# FPGA_RGMII_Misc.net
KiCad netlist of a schematic drawn in Altium Designer
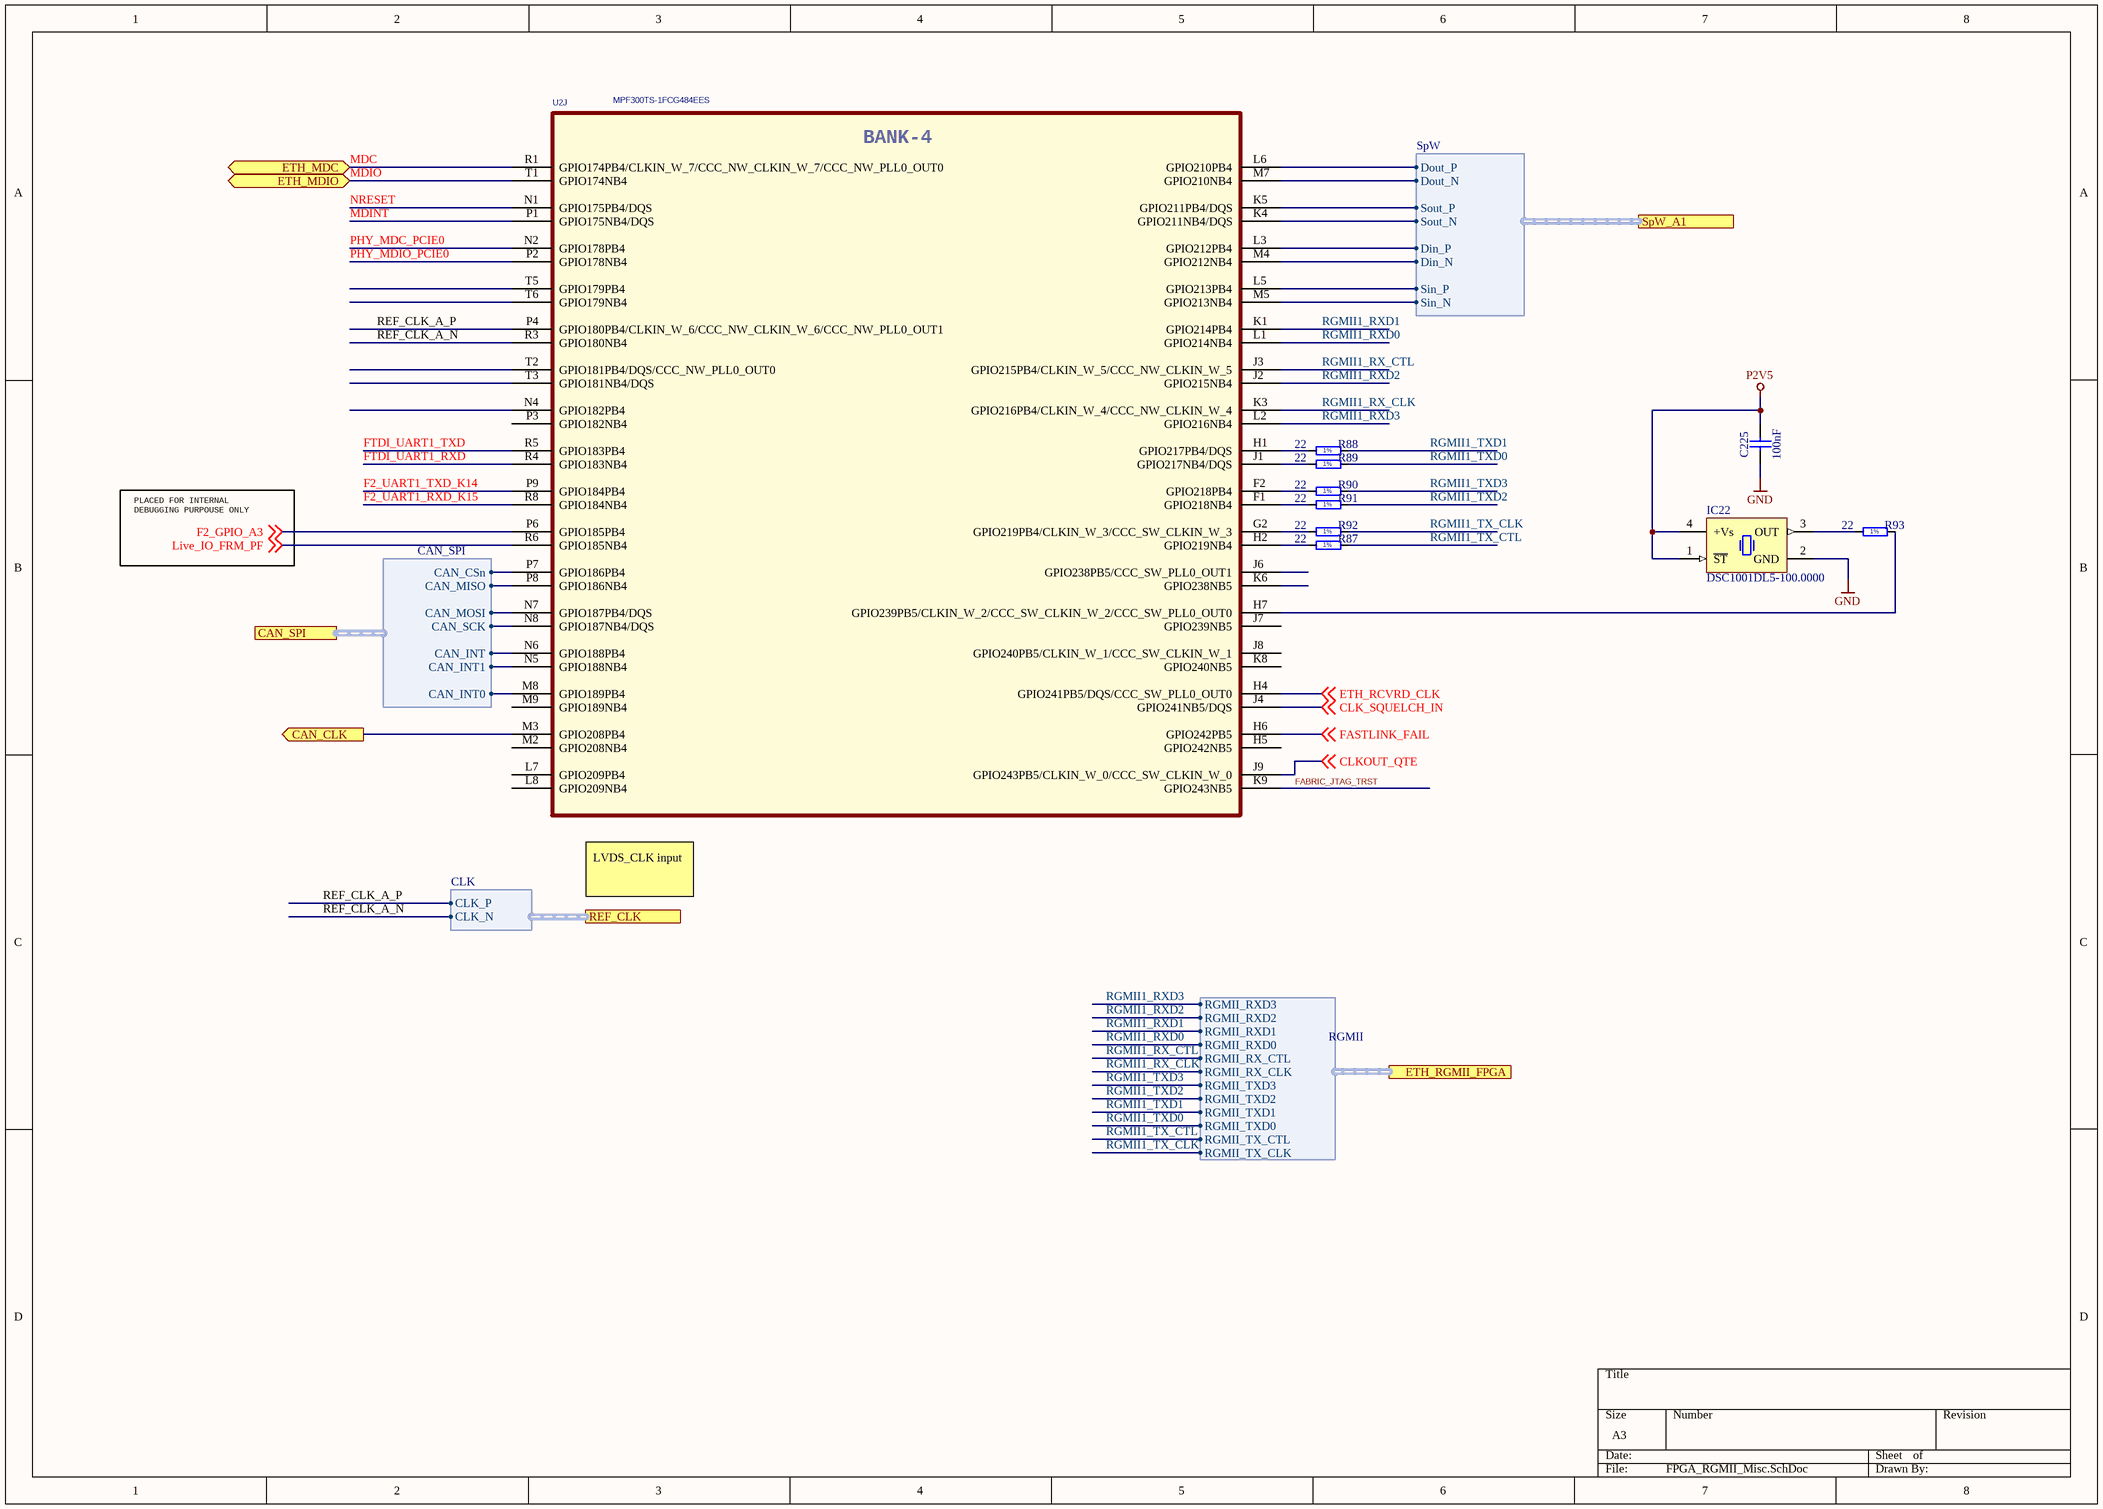
[diagram p0: FPGA_RGMII_Misc.SchDoc]

(export (version "E")
  (design (tool "Eeschema 10.0.6"))
  (components
    (comp (ref "C225")
      (value "100nF")
      (footprint "CAPC0603X33N")
      (description "Non-polarised capacitor")
      (fields
        (field (name "PART NUMBER") "CC0201_100NF_6.3V_10%_X5R")
        (field (name "MANUFACTURER") "GENERIC")
        (field (name "AUTHOR") "CERN DEM JLC")
      )
      (libsource (lib "Capacitors") (part "Capacitor - non polarized"))
    )
    (comp (ref "IC22")
      (value "DSC1001DL5-100.0000")
      (footprint "OSC_MICREL_2520")
      (description "MEMS 100MHz oscillator")
      (fields (field (name "MANUFACTURER") "Micrel"))
      (libsource (lib "LIBRARY_SCH") (part "OSC_DSC1001DL5-100.0000"))
    )
    (comp (ref "R87")
      (value "22")
      (footprint "RESC1005X40N")
      (description "Resistor - 1%")
      (fields
        (field (name "PART NUMBER") "R0402_22R_1%_0.0625W_100PPM")
        (field (name "POWER") "0.0625W")
        (field (name "AUTHOR") "CERN DEM JLC")
      )
      (libsource (lib "Resistors") (part "Resistor - 1%"))
    )
    (comp (ref "R88")
      (value "22")
      (footprint "RESC1005X40N")
      (description "Resistor - 1%")
      (fields
        (field (name "PART NUMBER") "R0402_22R_1%_0.0625W_100PPM")
        (field (name "POWER") "0.0625W")
        (field (name "AUTHOR") "CERN DEM JLC")
      )
      (libsource (lib "Resistors") (part "Resistor - 1%"))
    )
    (comp (ref "R89")
      (value "22")
      (footprint "RESC1005X40N")
      (description "Resistor - 1%")
      (fields
        (field (name "PART NUMBER") "R0402_22R_1%_0.0625W_100PPM")
        (field (name "POWER") "0.0625W")
        (field (name "AUTHOR") "CERN DEM JLC")
      )
      (libsource (lib "Resistors") (part "Resistor - 1%"))
    )
    (comp (ref "R90")
      (value "22")
      (footprint "RESC1005X40N")
      (description "Resistor - 1%")
      (fields
        (field (name "PART NUMBER") "R0402_22R_1%_0.0625W_100PPM")
        (field (name "POWER") "0.0625W")
        (field (name "AUTHOR") "CERN DEM JLC")
      )
      (libsource (lib "Resistors") (part "Resistor - 1%"))
    )
    (comp (ref "R91")
      (value "22")
      (footprint "RESC1005X40N")
      (description "Resistor - 1%")
      (fields
        (field (name "PART NUMBER") "R0402_22R_1%_0.0625W_100PPM")
        (field (name "POWER") "0.0625W")
        (field (name "AUTHOR") "CERN DEM JLC")
      )
      (libsource (lib "Resistors") (part "Resistor - 1%"))
    )
    (comp (ref "R92")
      (value "22")
      (footprint "RESC1005X40N")
      (description "Resistor - 1%")
      (fields
        (field (name "PART NUMBER") "R0402_22R_1%_0.0625W_100PPM")
        (field (name "POWER") "0.0625W")
        (field (name "AUTHOR") "CERN DEM JLC")
      )
      (libsource (lib "Resistors") (part "Resistor - 1%"))
    )
    (comp (ref "R93")
      (value "22")
      (footprint "RESC1005X40N")
      (description "Resistor - 1%")
      (fields
        (field (name "PART NUMBER") "R0402_22R_1%_0.0625W_100PPM")
        (field (name "POWER") "0.0625W")
        (field (name "AUTHOR") "CERN DEM JLC")
      )
      (libsource (lib "Resistors") (part "Resistor - 1%"))
    )
    (comp (ref "U2")
      (value "MPF300TS-1FCG484EES")
      (footprint "BGA484C100P22X22_2300X2300X320")
      (description "FCG484,23mmX23mm,1.0mm pitch")
      (fields (field (name "MANUFACTURER") "Microsemi") (field (name "PART NUMBER") "MPF300TS-1FCG484I"))
      (libsource (lib "LIBRARY_SCH") (part "FPGA_MPF300T-FCG484"))
    )
  )
  (nets
    (net (code "5") (name "/CAN_CLK") (class "Default")
      (node (ref "U2") (pin "M3") (pinfunction "GPIO208PB4_M3") (pintype "passive"))
    )
    (net (code "6") (name "/CAN_CSn") (class "Default")
      (node (ref "U2") (pin "P7") (pinfunction "GPIO186PB4_P7") (pintype "passive"))
    )
    (net (code "7") (name "/CAN_INT") (class "Default")
      (node (ref "U2") (pin "N6") (pinfunction "GPIO188PB4_N6") (pintype "passive"))
    )
    (net (code "8") (name "/CAN_INT0") (class "Default")
      (node (ref "U2") (pin "M8") (pinfunction "GPIO189PB4_M8") (pintype "passive"))
    )
    (net (code "9") (name "/CAN_INT1") (class "Default")
      (node (ref "U2") (pin "N5") (pinfunction "GPIO188NB4_N5") (pintype "passive"))
    )
    (net (code "10") (name "/CAN_MISO") (class "Default")
      (node (ref "U2") (pin "P8") (pinfunction "GPIO186NB4_P8") (pintype "passive"))
    )
    (net (code "11") (name "/CAN_MOSI") (class "Default")
      (node (ref "U2") (pin "N7") (pinfunction "GPIO187PB4/DQS_N7") (pintype "passive"))
    )
    (net (code "12") (name "/CAN_SCK") (class "Default")
      (node (ref "U2") (pin "N8") (pinfunction "GPIO187NB4/DQS_N8") (pintype "passive"))
    )
    (net (code "13") (name "/Din_N") (class "Default")
      (node (ref "U2") (pin "M4") (pinfunction "GPIO212NB4_M4") (pintype "passive"))
    )
    (net (code "14") (name "/Din_P") (class "Default")
      (node (ref "U2") (pin "L3") (pinfunction "GPIO212PB4_L3") (pintype "passive"))
    )
    (net (code "15") (name "/Dout_N") (class "Default")
      (node (ref "U2") (pin "M7") (pinfunction "GPIO210NB4_M7") (pintype "passive"))
    )
    (net (code "16") (name "/Dout_P") (class "Default")
      (node (ref "U2") (pin "L6") (pinfunction "GPIO210PB4_L6") (pintype "passive"))
    )
    (net (code "17") (name "/F2_UART1_RXD_K15") (class "Default")
      (node (ref "U2") (pin "R8") (pinfunction "GPIO184NB4_R8") (pintype "passive"))
    )
    (net (code "18") (name "/F2_UART1_TXD_K14") (class "Default")
      (node (ref "U2") (pin "P9") (pinfunction "GPIO184PB4_P9") (pintype "passive"))
    )
    (net (code "19") (name "/FABRIC_JTAG_TRST") (class "Default")
      (node (ref "U2") (pin "K9") (pinfunction "GPIO243NB5_K9") (pintype "passive"))
    )
    (net (code "20") (name "/FTDI_UART1_RXD") (class "Default")
      (node (ref "U2") (pin "R4") (pinfunction "GPIO183NB4_R4") (pintype "passive"))
    )
    (net (code "21") (name "/FTDI_UART1_TXD") (class "Default")
      (node (ref "U2") (pin "R5") (pinfunction "GPIO183PB4_R5") (pintype "passive"))
    )
    (net (code "22") (name "/MDC") (class "Default")
      (node (ref "U2") (pin "R1") (pinfunction "GPIO174PB4/CLKIN_W_7/CCC_NW_CLKIN_W_7/CCC_NW_PLL0_OUT0_R1") (pintype "passive"))
    )
    (net (code "23") (name "/MDINT") (class "Default")
      (node (ref "U2") (pin "P1") (pinfunction "GPIO175NB4/DQS_P1") (pintype "passive"))
    )
    (net (code "24") (name "/MDIO") (class "Default")
      (node (ref "U2") (pin "T1") (pinfunction "GPIO174NB4_T1") (pintype "passive"))
    )
    (net (code "25") (name "/NRESET") (class "Default")
      (node (ref "U2") (pin "N1") (pinfunction "GPIO175PB4/DQS_N1") (pintype "passive"))
    )
    (net (code "26") (name "/PHY_MDC_PCIE0") (class "Default")
      (node (ref "U2") (pin "N2") (pinfunction "GPIO178PB4_N2") (pintype "passive"))
    )
    (net (code "27") (name "/PHY_MDIO_PCIE0") (class "Default")
      (node (ref "U2") (pin "P2") (pinfunction "GPIO178NB4_P2") (pintype "passive"))
    )
    (net (code "28") (name "/REF_CLK_A_N") (class "Default")
      (node (ref "U2") (pin "R3") (pinfunction "GPIO180NB4_R3") (pintype "passive"))
    )
    (net (code "29") (name "/REF_CLK_A_P") (class "Default")
      (node (ref "U2") (pin "P4") (pinfunction "GPIO180PB4/CLKIN_W_6/CCC_NW_CLKIN_W_6/CCC_NW_PLL0_OUT1_P4") (pintype "passive"))
    )
    (net (code "30") (name "/RGMII1_RXD0") (class "Default")
      (node (ref "U2") (pin "L1") (pinfunction "GPIO214NB4_L1") (pintype "passive"))
    )
    (net (code "31") (name "/RGMII1_RXD1") (class "Default")
      (node (ref "U2") (pin "K1") (pinfunction "GPIO214PB4_K1") (pintype "passive"))
    )
    (net (code "32") (name "/RGMII1_RXD2") (class "Default")
      (node (ref "U2") (pin "J2") (pinfunction "GPIO215NB4_J2") (pintype "passive"))
    )
    (net (code "33") (name "/RGMII1_RXD3") (class "Default")
      (node (ref "U2") (pin "L2") (pinfunction "GPIO216NB4_L2") (pintype "passive"))
    )
    (net (code "34") (name "/RGMII1_RX_CLK") (class "Default")
      (node (ref "U2") (pin "K3") (pinfunction "GPIO216PB4/CLKIN_W_4/CCC_NW_CLKIN_W_4_K3") (pintype "passive"))
    )
    (net (code "35") (name "/RGMII1_RX_CTL") (class "Default")
      (node (ref "U2") (pin "J3") (pinfunction "GPIO215PB4/CLKIN_W_5/CCC_NW_CLKIN_W_5_J3") (pintype "passive"))
    )
    (net (code "36") (name "/RGMII1_TXD0") (class "Default")
      (node (ref "R89") (pin "2") (pinfunction "2_2") (pintype "passive"))
    )
    (net (code "37") (name "/RGMII1_TXD1") (class "Default")
      (node (ref "R88") (pin "2") (pinfunction "2_2") (pintype "passive"))
    )
    (net (code "38") (name "/RGMII1_TXD2") (class "Default")
      (node (ref "R91") (pin "2") (pinfunction "2_2") (pintype "passive"))
    )
    (net (code "39") (name "/RGMII1_TXD3") (class "Default")
      (node (ref "R90") (pin "2") (pinfunction "2_2") (pintype "passive"))
    )
    (net (code "40") (name "/RGMII1_TX_CLK") (class "Default")
      (node (ref "R92") (pin "2") (pinfunction "2_2") (pintype "passive"))
    )
    (net (code "41") (name "/RGMII1_TX_CTL") (class "Default")
      (node (ref "R87") (pin "2") (pinfunction "2_2") (pintype "passive"))
    )
    (net (code "42") (name "/Sin_N") (class "Default")
      (node (ref "U2") (pin "M5") (pinfunction "GPIO213NB4_M5") (pintype "passive"))
    )
    (net (code "43") (name "/Sin_P") (class "Default")
      (node (ref "U2") (pin "L5") (pinfunction "GPIO213PB4_L5") (pintype "passive"))
    )
    (net (code "44") (name "/Sout_N") (class "Default")
      (node (ref "U2") (pin "K4") (pinfunction "GPIO211NB4/DQS_K4") (pintype "passive"))
    )
    (net (code "45") (name "/Sout_P") (class "Default")
      (node (ref "U2") (pin "K5") (pinfunction "GPIO211PB4/DQS_K5") (pintype "passive"))
    )
    (net (code "50") (name "CLKOUT_QTE") (class "Default")
      (node (ref "U2") (pin "J9") (pinfunction "GPIO243PB5/CLKIN_W_0/CCC_SW_CLKIN_W_0_J9") (pintype "passive"))
    )
    (net (code "51") (name "CLK_SQUELCH_IN") (class "Default")
      (node (ref "U2") (pin "J4") (pinfunction "GPIO241NB5/DQS_J4") (pintype "passive"))
    )
    (net (code "52") (name "ETH_RCVRD_CLK") (class "Default")
      (node (ref "U2") (pin "H4") (pinfunction "GPIO241PB5/DQS/CCC_SW_PLL0_OUT0_H4") (pintype "passive"))
    )
    (net (code "53") (name "F2_GPIO_A3") (class "Default")
      (node (ref "U2") (pin "P6") (pinfunction "GPIO185PB4_P6") (pintype "passive"))
    )
    (net (code "54") (name "FASTLINK_FAIL") (class "Default")
      (node (ref "U2") (pin "H6") (pinfunction "GPIO242PB5_H6") (pintype "passive"))
    )
    (net (code "55") (name "GND") (class "Default")
      (node (ref "C225") (pin "1") (pinfunction "1_1") (pintype "passive"))
      (node (ref "IC22") (pin "2") (pinfunction "GND_2") (pintype "power_in"))
    )
    (net (code "56") (name "Live_IO_FRM_PF") (class "Default")
      (node (ref "U2") (pin "R6") (pinfunction "GPIO185NB4_R6") (pintype "passive"))
    )
    (net (code "57") (name "Net-(IC22-OUT)") (class "Default")
      (node (ref "IC22") (pin "3") (pinfunction "OUT_3") (pintype "output"))
      (node (ref "R93") (pin "1") (pinfunction "1_1") (pintype "passive"))
    )
    (net (code "58") (name "Net-(U2J-GPIO217NB4{slash}DQS)") (class "Default")
      (node (ref "R89") (pin "1") (pinfunction "1_1") (pintype "passive"))
      (node (ref "U2") (pin "J1") (pinfunction "GPIO217NB4/DQS_J1") (pintype "passive"))
    )
    (net (code "59") (name "Net-(U2J-GPIO217PB4{slash}DQS)") (class "Default")
      (node (ref "R88") (pin "1") (pinfunction "1_1") (pintype "passive"))
      (node (ref "U2") (pin "H1") (pinfunction "GPIO217PB4/DQS_H1") (pintype "passive"))
    )
    (net (code "60") (name "Net-(U2J-GPIO218NB4)") (class "Default")
      (node (ref "R91") (pin "1") (pinfunction "1_1") (pintype "passive"))
      (node (ref "U2") (pin "F1") (pinfunction "GPIO218NB4_F1") (pintype "passive"))
    )
    (net (code "61") (name "Net-(U2J-GPIO218PB4)") (class "Default")
      (node (ref "R90") (pin "1") (pinfunction "1_1") (pintype "passive"))
      (node (ref "U2") (pin "F2") (pinfunction "GPIO218PB4_F2") (pintype "passive"))
    )
    (net (code "62") (name "Net-(U2J-GPIO219NB4)") (class "Default")
      (node (ref "R87") (pin "1") (pinfunction "1_1") (pintype "passive"))
      (node (ref "U2") (pin "H2") (pinfunction "GPIO219NB4_H2") (pintype "passive"))
    )
    (net (code "63") (name "Net-(U2J-GPIO219PB4{slash}CLKIN_W_3{slash}CCC_SW_CLKIN_W_3)") (class "Default")
      (node (ref "R92") (pin "1") (pinfunction "1_1") (pintype "passive"))
      (node (ref "U2") (pin "G2") (pinfunction "GPIO219PB4/CLKIN_W_3/CCC_SW_CLKIN_W_3_G2") (pintype "passive"))
    )
    (net (code "64") (name "Net-(U2J-GPIO239PB5{slash}CLKIN_W_2{slash}CCC_SW_CLKIN_W_2{slash}CCC_SW_PLL0_OUT0)") (class "Default")
      (node (ref "R93") (pin "2") (pinfunction "2_2") (pintype "passive"))
      (node (ref "U2") (pin "H7") (pinfunction "GPIO239PB5/CLKIN_W_2/CCC_SW_CLKIN_W_2/CCC_SW_PLL0_OUT0_H7") (pintype "passive"))
    )
    (net (code "65") (name "P2V5") (class "Default")
      (node (ref "C225") (pin "2") (pinfunction "2_2") (pintype "passive"))
      (node (ref "IC22") (pin "1") (pinfunction "ST_1") (pintype "input"))
      (node (ref "IC22") (pin "4") (pinfunction "+Vs_4") (pintype "power_in"))
    )
    (net (code "66") (name "unconnected-(U2J-GPIO179NB4-PadT6)") (class "Default")
      (node (ref "U2") (pin "T6") (pinfunction "GPIO179NB4_T6") (pintype "passive"))
    )
    (net (code "67") (name "unconnected-(U2J-GPIO179PB4-PadT5)") (class "Default")
      (node (ref "U2") (pin "T5") (pinfunction "GPIO179PB4_T5") (pintype "passive"))
    )
    (net (code "68") (name "unconnected-(U2J-GPIO181NB4{slash}DQS-PadT3)") (class "Default")
      (node (ref "U2") (pin "T3") (pinfunction "GPIO181NB4/DQS_T3") (pintype "passive"))
    )
    (net (code "69") (name "unconnected-(U2J-GPIO181PB4{slash}DQS{slash}CCC_NW_PLL0_OUT0-PadT2)") (class "Default")
      (node (ref "U2") (pin "T2") (pinfunction "GPIO181PB4/DQS/CCC_NW_PLL0_OUT0_T2") (pintype "passive"))
    )
    (net (code "70") (name "unconnected-(U2J-GPIO182NB4-PadP3)") (class "Default")
      (node (ref "U2") (pin "P3") (pinfunction "GPIO182NB4_P3") (pintype "passive"))
    )
    (net (code "71") (name "unconnected-(U2J-GPIO182PB4-PadN4)") (class "Default")
      (node (ref "U2") (pin "N4") (pinfunction "GPIO182PB4_N4") (pintype "passive"))
    )
    (net (code "72") (name "unconnected-(U2J-GPIO189NB4-PadM9)") (class "Default")
      (node (ref "U2") (pin "M9") (pinfunction "GPIO189NB4_M9") (pintype "passive"))
    )
    (net (code "73") (name "unconnected-(U2J-GPIO208NB4-PadM2)") (class "Default")
      (node (ref "U2") (pin "M2") (pinfunction "GPIO208NB4_M2") (pintype "passive"))
    )
    (net (code "74") (name "unconnected-(U2J-GPIO209NB4-PadL8)") (class "Default")
      (node (ref "U2") (pin "L8") (pinfunction "GPIO209NB4_L8") (pintype "passive"))
    )
    (net (code "75") (name "unconnected-(U2J-GPIO209PB4-PadL7)") (class "Default")
      (node (ref "U2") (pin "L7") (pinfunction "GPIO209PB4_L7") (pintype "passive"))
    )
    (net (code "76") (name "unconnected-(U2J-GPIO238NB5-PadK6)") (class "Default")
      (node (ref "U2") (pin "K6") (pinfunction "GPIO238NB5_K6") (pintype "passive"))
    )
    (net (code "77") (name "unconnected-(U2J-GPIO238PB5{slash}CCC_SW_PLL0_OUT1-PadJ6)") (class "Default")
      (node (ref "U2") (pin "J6") (pinfunction "GPIO238PB5/CCC_SW_PLL0_OUT1_J6") (pintype "passive"))
    )
    (net (code "78") (name "unconnected-(U2J-GPIO239NB5-PadJ7)") (class "Default")
      (node (ref "U2") (pin "J7") (pinfunction "GPIO239NB5_J7") (pintype "passive"))
    )
    (net (code "79") (name "unconnected-(U2J-GPIO240NB5-PadK8)") (class "Default")
      (node (ref "U2") (pin "K8") (pinfunction "GPIO240NB5_K8") (pintype "passive"))
    )
    (net (code "80") (name "unconnected-(U2J-GPIO240PB5{slash}CLKIN_W_1{slash}CCC_SW_CLKIN_W_1-PadJ8)") (class "Default")
      (node (ref "U2") (pin "J8") (pinfunction "GPIO240PB5/CLKIN_W_1/CCC_SW_CLKIN_W_1_J8") (pintype "passive"))
    )
    (net (code "81") (name "unconnected-(U2J-GPIO242NB5-PadH5)") (class "Default")
      (node (ref "U2") (pin "H5") (pinfunction "GPIO242NB5_H5") (pintype "passive"))
    )
  )
)
